# ADC.net
KiCad netlist of a schematic drawn in Altium Designer
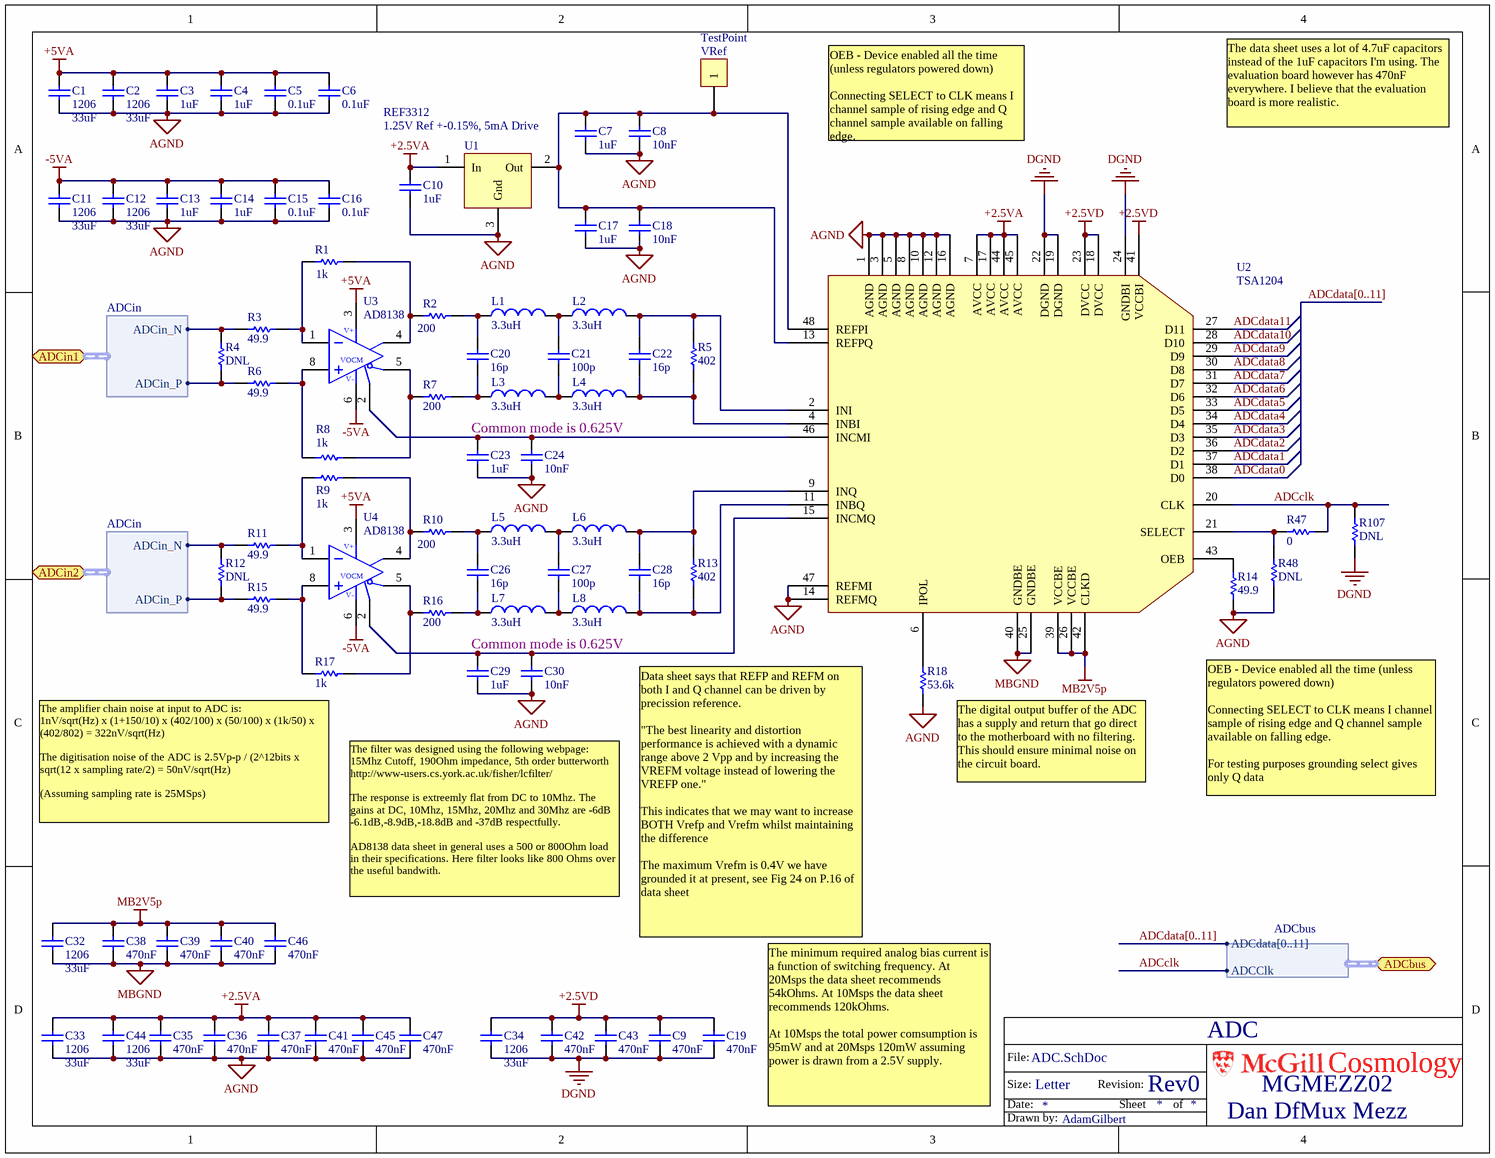
[diagram p0: ADC.SchDoc]

(export (version "E")
  (design (tool "Eeschema 10.0.6"))
  (components
    (comp (ref "C1")
      (value "33uF")
      (footprint "1206")
      (description "Capacitor, Ceramic, 1210")
      (fields
        (field (name "MANUFACTURER") "TDK Corporation")
        (field (name "MANUFACTURERS PART NUMBER") "C3216X5R1E336M")
      )
      (libsource (lib "MGMEZZ04") (part "CAP 1210"))
    )
    (comp (ref "C2")
      (value "33uF")
      (footprint "1206")
      (description "Capacitor, Ceramic, 1210")
      (fields
        (field (name "MANUFACTURER") "TDK Corporation")
        (field (name "MANUFACTURERS PART NUMBER") "C3216X5R1E336M")
      )
      (libsource (lib "MGMEZZ04") (part "CAP 1210"))
    )
    (comp (ref "C3")
      (value "1uF")
      (footprint "0603")
      (description "Capacitor, Ceramic, 0603")
      (fields
        (field (name "MANUFACTURER") "Generic")
        (field (name "MANUFACTURERS PART NUMBER") "e.g C1608X7R1C105K")
      )
      (libsource (lib "MGMEZZ04") (part "CAP 0603"))
    )
    (comp (ref "C4")
      (value "1uF")
      (footprint "0603")
      (description "Capacitor, Ceramic, 0603")
      (fields
        (field (name "MANUFACTURER") "Generic")
        (field (name "MANUFACTURERS PART NUMBER") "e.g C1608X7R1C105K")
      )
      (libsource (lib "MGMEZZ04") (part "CAP 0603"))
    )
    (comp (ref "C5")
      (value "0.1uF")
      (footprint "0603")
      (description "Capacitor, Ceramic, 0603")
      (fields (field (name "MANUFACTURER") "Generic"))
      (libsource (lib "MGMEZZ04") (part "CAP 0603"))
    )
    (comp (ref "C6")
      (value "0.1uF")
      (footprint "0603")
      (description "Capacitor, Ceramic, 0603")
      (fields (field (name "MANUFACTURER") "Generic"))
      (libsource (lib "MGMEZZ04") (part "CAP 0603"))
    )
    (comp (ref "C7")
      (value "1uF")
      (footprint "0603")
      (description "Capacitor, Ceramic, 0603")
      (fields
        (field (name "MANUFACTURER") "Generic")
        (field (name "MANUFACTURERS PART NUMBER") "e.g C1608X7R1C105K")
      )
      (libsource (lib "MGMEZZ04") (part "CAP 0603"))
    )
    (comp (ref "C8")
      (value "10nF")
      (footprint "0603")
      (description "Capacitor, Ceramic, 0603")
      (fields (field (name "MANUFACTURER") "Generic"))
      (libsource (lib "MGMEZZ04") (part "CAP 0603"))
    )
    (comp (ref "C9")
      (value "470nF")
      (footprint "0603")
      (description "Capacitor, Ceramic, 0603")
      (fields (field (name "MANUFACTURER") "Generic"))
      (libsource (lib "MGMEZZ04") (part "CAP 0603"))
    )
    (comp (ref "C10")
      (value "1uF")
      (footprint "0603")
      (description "Capacitor, Ceramic, 0603")
      (fields
        (field (name "MANUFACTURER") "Generic")
        (field (name "MANUFACTURERS PART NUMBER") "e.g C1608X7R1C105K")
      )
      (libsource (lib "MGMEZZ04") (part "CAP 0603"))
    )
    (comp (ref "C11")
      (value "33uF")
      (footprint "1206")
      (description "Capacitor, Ceramic, 1210")
      (fields
        (field (name "MANUFACTURER") "TDK Corporation")
        (field (name "MANUFACTURERS PART NUMBER") "C3216X5R1E336M")
      )
      (libsource (lib "MGMEZZ04") (part "CAP 1210"))
    )
    (comp (ref "C12")
      (value "33uF")
      (footprint "1206")
      (description "Capacitor, Ceramic, 1210")
      (fields
        (field (name "MANUFACTURER") "TDK Corporation")
        (field (name "MANUFACTURERS PART NUMBER") "C3216X5R1E336M")
      )
      (libsource (lib "MGMEZZ04") (part "CAP 1210"))
    )
    (comp (ref "C13")
      (value "1uF")
      (footprint "0603")
      (description "Capacitor, Ceramic, 0603")
      (fields
        (field (name "MANUFACTURER") "Generic")
        (field (name "MANUFACTURERS PART NUMBER") "e.g C1608X7R1C105K")
      )
      (libsource (lib "MGMEZZ04") (part "CAP 0603"))
    )
    (comp (ref "C14")
      (value "1uF")
      (footprint "0603")
      (description "Capacitor, Ceramic, 0603")
      (fields
        (field (name "MANUFACTURER") "Generic")
        (field (name "MANUFACTURERS PART NUMBER") "e.g C1608X7R1C105K")
      )
      (libsource (lib "MGMEZZ04") (part "CAP 0603"))
    )
    (comp (ref "C15")
      (value "0.1uF")
      (footprint "0603")
      (description "Capacitor, Ceramic, 0603")
      (fields (field (name "MANUFACTURER") "Generic"))
      (libsource (lib "MGMEZZ04") (part "CAP 0603"))
    )
    (comp (ref "C16")
      (value "0.1uF")
      (footprint "0603")
      (description "Capacitor, Ceramic, 0603")
      (fields (field (name "MANUFACTURER") "Generic"))
      (libsource (lib "MGMEZZ04") (part "CAP 0603"))
    )
    (comp (ref "C17")
      (value "1uF")
      (footprint "0603")
      (description "Capacitor, Ceramic, 0603")
      (fields
        (field (name "MANUFACTURER") "Generic")
        (field (name "MANUFACTURERS PART NUMBER") "e.g C1608X7R1C105K")
      )
      (libsource (lib "MGMEZZ04") (part "CAP 0603"))
    )
    (comp (ref "C18")
      (value "10nF")
      (footprint "0603")
      (description "Capacitor, Ceramic, 0603")
      (fields (field (name "MANUFACTURER") "Generic"))
      (libsource (lib "MGMEZZ04") (part "CAP 0603"))
    )
    (comp (ref "C19")
      (value "470nF")
      (footprint "0603")
      (description "Capacitor, Ceramic, 0603")
      (fields (field (name "MANUFACTURER") "Generic"))
      (libsource (lib "MGMEZZ04") (part "CAP 0603"))
    )
    (comp (ref "C20")
      (value "16p")
      (footprint "0603")
      (description "Capacitor, Ceramic, 0603")
      (fields (field (name "MANUFACTURER") "Generic"))
      (libsource (lib "MGMEZZ04") (part "CAP 0603"))
    )
    (comp (ref "C21")
      (value "100p")
      (footprint "0603")
      (description "Capacitor, Ceramic, 0603")
      (fields (field (name "MANUFACTURER") "Generic"))
      (libsource (lib "MGMEZZ04") (part "CAP 0603"))
    )
    (comp (ref "C22")
      (value "16p")
      (footprint "0603")
      (description "Capacitor, Ceramic, 0603")
      (fields (field (name "MANUFACTURER") "Generic"))
      (libsource (lib "MGMEZZ04") (part "CAP 0603"))
    )
    (comp (ref "C23")
      (value "1uF")
      (footprint "0603")
      (description "Capacitor, Ceramic, 0603")
      (fields
        (field (name "MANUFACTURER") "Generic")
        (field (name "MANUFACTURERS PART NUMBER") "e.g C1608X7R1C105K")
      )
      (libsource (lib "MGMEZZ04") (part "CAP 0603"))
    )
    (comp (ref "C24")
      (value "10nF")
      (footprint "0603")
      (description "Capacitor, Ceramic, 0603")
      (fields (field (name "MANUFACTURER") "Generic"))
      (libsource (lib "MGMEZZ04") (part "CAP 0603"))
    )
    (comp (ref "C26")
      (value "16p")
      (footprint "0603")
      (description "Capacitor, Ceramic, 0603")
      (fields (field (name "MANUFACTURER") "Generic"))
      (libsource (lib "MGMEZZ04") (part "CAP 0603"))
    )
    (comp (ref "C27")
      (value "100p")
      (footprint "0603")
      (description "Capacitor, Ceramic, 0603")
      (fields (field (name "MANUFACTURER") "Generic"))
      (libsource (lib "MGMEZZ04") (part "CAP 0603"))
    )
    (comp (ref "C28")
      (value "16p")
      (footprint "0603")
      (description "Capacitor, Ceramic, 0603")
      (fields (field (name "MANUFACTURER") "Generic"))
      (libsource (lib "MGMEZZ04") (part "CAP 0603"))
    )
    (comp (ref "C29")
      (value "1uF")
      (footprint "0603")
      (description "Capacitor, Ceramic, 0603")
      (fields
        (field (name "MANUFACTURER") "Generic")
        (field (name "MANUFACTURERS PART NUMBER") "e.g C1608X7R1C105K")
      )
      (libsource (lib "MGMEZZ04") (part "CAP 0603"))
    )
    (comp (ref "C30")
      (value "10nF")
      (footprint "0603")
      (description "Capacitor, Ceramic, 0603")
      (fields (field (name "MANUFACTURER") "Generic"))
      (libsource (lib "MGMEZZ04") (part "CAP 0603"))
    )
    (comp (ref "C32")
      (value "33uF")
      (footprint "1206")
      (description "Capacitor, Ceramic, 1210")
      (fields
        (field (name "MANUFACTURER") "TDK Corporation")
        (field (name "MANUFACTURERS PART NUMBER") "C3216X5R1E336M")
      )
      (libsource (lib "MGMEZZ04") (part "CAP 1210"))
    )
    (comp (ref "C33")
      (value "33uF")
      (footprint "1206")
      (description "Capacitor, Ceramic, 1210")
      (fields
        (field (name "MANUFACTURER") "TDK Corporation")
        (field (name "MANUFACTURERS PART NUMBER") "C3216X5R1E336M")
      )
      (libsource (lib "MGMEZZ04") (part "CAP 1210"))
    )
    (comp (ref "C34")
      (value "33uF")
      (footprint "1206")
      (description "Capacitor, Ceramic, 1210")
      (fields
        (field (name "MANUFACTURER") "TDK Corporation")
        (field (name "MANUFACTURERS PART NUMBER") "C3216X5R1E336M")
      )
      (libsource (lib "MGMEZZ04") (part "CAP 1210"))
    )
    (comp (ref "C35")
      (value "470nF")
      (footprint "0603")
      (description "Capacitor, Ceramic, 0603")
      (fields (field (name "MANUFACTURER") "Generic"))
      (libsource (lib "MGMEZZ04") (part "CAP 0603"))
    )
    (comp (ref "C36")
      (value "470nF")
      (footprint "0603")
      (description "Capacitor, Ceramic, 0603")
      (fields (field (name "MANUFACTURER") "Generic"))
      (libsource (lib "MGMEZZ04") (part "CAP 0603"))
    )
    (comp (ref "C37")
      (value "470nF")
      (footprint "0603")
      (description "Capacitor, Ceramic, 0603")
      (fields (field (name "MANUFACTURER") "Generic"))
      (libsource (lib "MGMEZZ04") (part "CAP 0603"))
    )
    (comp (ref "C38")
      (value "470nF")
      (footprint "0603")
      (description "Capacitor, Ceramic, 0603")
      (fields (field (name "MANUFACTURER") "Generic"))
      (libsource (lib "MGMEZZ04") (part "CAP 0603"))
    )
    (comp (ref "C39")
      (value "470nF")
      (footprint "0603")
      (description "Capacitor, Ceramic, 0603")
      (fields (field (name "MANUFACTURER") "Generic"))
      (libsource (lib "MGMEZZ04") (part "CAP 0603"))
    )
    (comp (ref "C40")
      (value "470nF")
      (footprint "0603")
      (description "Capacitor, Ceramic, 0603")
      (fields (field (name "MANUFACTURER") "Generic"))
      (libsource (lib "MGMEZZ04") (part "CAP 0603"))
    )
    (comp (ref "C41")
      (value "470nF")
      (footprint "0603")
      (description "Capacitor, Ceramic, 0603")
      (fields (field (name "MANUFACTURER") "Generic"))
      (libsource (lib "MGMEZZ04") (part "CAP 0603"))
    )
    (comp (ref "C42")
      (value "470nF")
      (footprint "0603")
      (description "Capacitor, Ceramic, 0603")
      (fields (field (name "MANUFACTURER") "Generic"))
      (libsource (lib "MGMEZZ04") (part "CAP 0603"))
    )
    (comp (ref "C43")
      (value "470nF")
      (footprint "0603")
      (description "Capacitor, Ceramic, 0603")
      (fields (field (name "MANUFACTURER") "Generic"))
      (libsource (lib "MGMEZZ04") (part "CAP 0603"))
    )
    (comp (ref "C44")
      (value "33uF")
      (footprint "1206")
      (description "Capacitor, Ceramic, 1210")
      (fields
        (field (name "MANUFACTURER") "TDK Corporation")
        (field (name "MANUFACTURERS PART NUMBER") "C3216X5R1E336M")
      )
      (libsource (lib "MGMEZZ04") (part "CAP 1210"))
    )
    (comp (ref "C45")
      (value "470nF")
      (footprint "0603")
      (description "Capacitor, Ceramic, 0603")
      (fields (field (name "MANUFACTURER") "Generic"))
      (libsource (lib "MGMEZZ04") (part "CAP 0603"))
    )
    (comp (ref "C46")
      (value "470nF")
      (footprint "0603")
      (description "Capacitor, Ceramic, 0603")
      (fields (field (name "MANUFACTURER") "Generic"))
      (libsource (lib "MGMEZZ04") (part "CAP 0603"))
    )
    (comp (ref "C47")
      (value "470nF")
      (footprint "0603")
      (description "Capacitor, Ceramic, 0603")
      (fields (field (name "MANUFACTURER") "Generic"))
      (libsource (lib "MGMEZZ04") (part "CAP 0603"))
    )
    (comp (ref "L1")
      (value "3.3uH")
      (footprint "0603")
      (description "Inductor 0603")
      (fields
        (field (name "MANUFACTURER") "TDK Coporation")
        (field (name "MANUFACTURERS PART NUMBER") "MLF1608A4R7K")
      )
      (libsource (lib "MGMEZZ04") (part "IND 0603"))
    )
    (comp (ref "L2")
      (value "3.3uH")
      (footprint "0603")
      (description "Inductor 0603")
      (fields
        (field (name "MANUFACTURER") "TDK Coporation")
        (field (name "MANUFACTURERS PART NUMBER") "MLF1608A4R7K")
      )
      (libsource (lib "MGMEZZ04") (part "IND 0603"))
    )
    (comp (ref "L3")
      (value "3.3uH")
      (footprint "0603")
      (description "Inductor 0603")
      (fields
        (field (name "MANUFACTURER") "TDK Coporation")
        (field (name "MANUFACTURERS PART NUMBER") "MLF1608A4R7K")
      )
      (libsource (lib "MGMEZZ04") (part "IND 0603"))
    )
    (comp (ref "L4")
      (value "3.3uH")
      (footprint "0603")
      (description "Inductor 0603")
      (fields
        (field (name "MANUFACTURER") "TDK Coporation")
        (field (name "MANUFACTURERS PART NUMBER") "MLF1608A4R7K")
      )
      (libsource (lib "MGMEZZ04") (part "IND 0603"))
    )
    (comp (ref "L5")
      (value "3.3uH")
      (footprint "0603")
      (description "Inductor 0603")
      (fields
        (field (name "MANUFACTURER") "TDK Coporation")
        (field (name "MANUFACTURERS PART NUMBER") "MLF1608A4R7K")
      )
      (libsource (lib "MGMEZZ04") (part "IND 0603"))
    )
    (comp (ref "L6")
      (value "3.3uH")
      (footprint "0603")
      (description "Inductor 0603")
      (fields
        (field (name "MANUFACTURER") "TDK Coporation")
        (field (name "MANUFACTURERS PART NUMBER") "MLF1608A4R7K")
      )
      (libsource (lib "MGMEZZ04") (part "IND 0603"))
    )
    (comp (ref "L7")
      (value "3.3uH")
      (footprint "0603")
      (description "Inductor 0603")
      (fields
        (field (name "MANUFACTURER") "TDK Coporation")
        (field (name "MANUFACTURERS PART NUMBER") "MLF1608A4R7K")
      )
      (libsource (lib "MGMEZZ04") (part "IND 0603"))
    )
    (comp (ref "L8")
      (value "3.3uH")
      (footprint "0603")
      (description "Inductor 0603")
      (fields
        (field (name "MANUFACTURER") "TDK Coporation")
        (field (name "MANUFACTURERS PART NUMBER") "MLF1608A4R7K")
      )
      (libsource (lib "MGMEZZ04") (part "IND 0603"))
    )
    (comp (ref "R1")
      (value "1k")
      (footprint "0603")
      (description "Resistor")
      (fields (field (name "MANUFACTURER") "Generic"))
      (libsource (lib "MGMEZZ04") (part "RES 0603"))
    )
    (comp (ref "R2")
      (value "200")
      (footprint "0603")
      (description "Resistor")
      (fields (field (name "MANUFACTURER") "Generic"))
      (libsource (lib "MGMEZZ04") (part "RES 0603"))
    )
    (comp (ref "R3")
      (value "49.9")
      (footprint "0603")
      (description "Resistor")
      (fields (field (name "MANUFACTURER") "Generic"))
      (libsource (lib "MGMEZZ04") (part "RES 0603"))
    )
    (comp (ref "R4")
      (value "DNL")
      (footprint "0603")
      (description "Resistor")
      (fields (field (name "MANUFACTURER") "Generic"))
      (libsource (lib "MGMEZZ04") (part "RES 0603"))
    )
    (comp (ref "R5")
      (value "402")
      (footprint "0603")
      (description "Resistor")
      (fields (field (name "MANUFACTURER") "Generic"))
      (libsource (lib "MGMEZZ04") (part "RES 0603"))
    )
    (comp (ref "R6")
      (value "49.9")
      (footprint "0603")
      (description "Resistor")
      (fields (field (name "MANUFACTURER") "Generic"))
      (libsource (lib "MGMEZZ04") (part "RES 0603"))
    )
    (comp (ref "R7")
      (value "200")
      (footprint "0603")
      (description "Resistor")
      (fields (field (name "MANUFACTURER") "Generic"))
      (libsource (lib "MGMEZZ04") (part "RES 0603"))
    )
    (comp (ref "R8")
      (value "1k")
      (footprint "0603")
      (description "Resistor")
      (fields (field (name "MANUFACTURER") "Generic"))
      (libsource (lib "MGMEZZ04") (part "RES 0603"))
    )
    (comp (ref "R9")
      (value "1k")
      (footprint "0603")
      (description "Resistor")
      (fields (field (name "MANUFACTURER") "Generic"))
      (libsource (lib "MGMEZZ04") (part "RES 0603"))
    )
    (comp (ref "R10")
      (value "200")
      (footprint "0603")
      (description "Resistor")
      (fields (field (name "MANUFACTURER") "Generic"))
      (libsource (lib "MGMEZZ04") (part "RES 0603"))
    )
    (comp (ref "R11")
      (value "49.9")
      (footprint "0603")
      (description "Resistor")
      (fields (field (name "MANUFACTURER") "Generic"))
      (libsource (lib "MGMEZZ04") (part "RES 0603"))
    )
    (comp (ref "R12")
      (value "DNL")
      (footprint "0603")
      (description "Resistor")
      (fields (field (name "MANUFACTURER") "Generic"))
      (libsource (lib "MGMEZZ04") (part "RES 0603"))
    )
    (comp (ref "R13")
      (value "402")
      (footprint "0603")
      (description "Resistor")
      (fields (field (name "MANUFACTURER") "Generic"))
      (libsource (lib "MGMEZZ04") (part "RES 0603"))
    )
    (comp (ref "R14")
      (value "49.9")
      (footprint "0603")
      (description "Resistor")
      (fields (field (name "MANUFACTURER") "Generic"))
      (libsource (lib "MGMEZZ04") (part "RES 0603"))
    )
    (comp (ref "R15")
      (value "49.9")
      (footprint "0603")
      (description "Resistor")
      (fields (field (name "MANUFACTURER") "Generic"))
      (libsource (lib "MGMEZZ04") (part "RES 0603"))
    )
    (comp (ref "R16")
      (value "200")
      (footprint "0603")
      (description "Resistor")
      (fields (field (name "MANUFACTURER") "Generic"))
      (libsource (lib "MGMEZZ04") (part "RES 0603"))
    )
    (comp (ref "R17")
      (value "1k")
      (footprint "0603")
      (description "Resistor")
      (fields (field (name "MANUFACTURER") "Generic"))
      (libsource (lib "MGMEZZ04") (part "RES 0603"))
    )
    (comp (ref "R18")
      (value "53.6k")
      (footprint "0603")
      (description "Resistor")
      (fields (field (name "MANUFACTURER") "Generic"))
      (libsource (lib "MGMEZZ04") (part "RES 0603"))
    )
    (comp (ref "R47")
      (value "0")
      (footprint "0603")
      (description "Resistor")
      (fields (field (name "MANUFACTURER") "Generic"))
      (libsource (lib "MGMEZZ04") (part "RES 0603"))
    )
    (comp (ref "R48")
      (value "DNL")
      (footprint "0603")
      (description "Resistor")
      (fields (field (name "MANUFACTURER") "Generic"))
      (libsource (lib "MGMEZZ04") (part "RES 0603"))
    )
    (comp (ref "R107")
      (value "DNL")
      (footprint "0603")
      (description "Resistor")
      (fields (field (name "MANUFACTURER") "Generic"))
      (libsource (lib "MGMEZZ04") (part "RES 0603"))
    )
    (comp (ref "U1")
      (value "REF3312")
      (footprint "SOT23")
      (description "1.25V Ref +-0.15%, 5mA Drive")
      (fields
        (field (name "MANUFACTURER") "Texas Instruments")
        (field (name "MANUFACTURERS PART NUMBER") "REF3312AIDBZT")
      )
      (libsource (lib "MGMEZZ04") (part "REF3312AIDBZT"))
    )
    (comp (ref "U2")
      (value "TSA1204")
      (footprint "TSQFP50P900X900X160-48N")
      (description "ADC 2-Channel 12bit")
      (fields
        (field (name "MANUFACTURERS PART NUMBER") "TSA1204IFT")
        (field (name "MANUFACTURER") "STMicroelectronics")
      )
      (libsource (lib "MGMEZZ04") (part "TSA1204"))
    )
    (comp (ref "U3")
      (value "AD8138")
      (footprint "SO8")
      (description "IC AMP DIFF LDIST LP 95MA 8SOIC")
      (fields
        (field (name "MANUFACTURER") "Analog Devices Inc")
        (field (name "MANUFACTURERS PART NUMBER") "AD8138ARZ")
      )
      (libsource (lib "MGMEZZ04") (part "AD8138"))
    )
    (comp (ref "U4")
      (value "AD8138")
      (footprint "SO8")
      (description "IC AMP DIFF LDIST LP 95MA 8SOIC")
      (fields
        (field (name "MANUFACTURER") "Analog Devices Inc")
        (field (name "MANUFACTURERS PART NUMBER") "AD8138ARZ")
      )
      (libsource (lib "MGMEZZ04") (part "AD8138"))
    )
    (comp (ref "VRef")
      (value "TestPoint")
      (footprint "TP-3520-SK")
      (description "TestPoint1")
      (libsource (lib "MGMEZZ04") (part "TestPoint"))
    )
  )
  (nets
    (net (code "3") (name "+2.5VA") (class "Default")
      (node (ref "C10") (pin "2") (pinfunction "2_2") (pintype "passive"))
      (node (ref "C33") (pin "2") (pinfunction "2_2") (pintype "passive"))
      (node (ref "C35") (pin "2") (pinfunction "2_2") (pintype "passive"))
      (node (ref "C36") (pin "2") (pinfunction "2_2") (pintype "passive"))
      (node (ref "C37") (pin "2") (pinfunction "2_2") (pintype "passive"))
      (node (ref "C41") (pin "2") (pinfunction "2_2") (pintype "passive"))
      (node (ref "C44") (pin "2") (pinfunction "2_2") (pintype "passive"))
      (node (ref "C45") (pin "2") (pinfunction "2_2") (pintype "passive"))
      (node (ref "C47") (pin "2") (pinfunction "2_2") (pintype "passive"))
      (node (ref "U1") (pin "1") (pinfunction "In_1") (pintype "passive"))
      (node (ref "U2") (pin "17") (pinfunction "AVCC_17") (pintype "passive"))
      (node (ref "U2") (pin "44") (pinfunction "AVCC_44") (pintype "passive"))
      (node (ref "U2") (pin "45") (pinfunction "AVCC_45") (pintype "passive"))
      (node (ref "U2") (pin "7") (pinfunction "AVCC_7") (pintype "passive"))
    )
    (net (code "4") (name "+2.5VD") (class "Default")
      (node (ref "C19") (pin "2") (pinfunction "2_2") (pintype "passive"))
      (node (ref "C34") (pin "2") (pinfunction "2_2") (pintype "passive"))
      (node (ref "C42") (pin "2") (pinfunction "2_2") (pintype "passive"))
      (node (ref "C43") (pin "2") (pinfunction "2_2") (pintype "passive"))
      (node (ref "C9") (pin "2") (pinfunction "2_2") (pintype "passive"))
      (node (ref "U2") (pin "18") (pinfunction "DVCC_18") (pintype "passive"))
      (node (ref "U2") (pin "23") (pinfunction "DVCC_23") (pintype "passive"))
      (node (ref "U2") (pin "41") (pinfunction "VCCBI_41") (pintype "passive"))
    )
    (net (code "5") (name "+5VA") (class "Default")
      (node (ref "C1") (pin "2") (pinfunction "2_2") (pintype "passive"))
      (node (ref "C2") (pin "2") (pinfunction "2_2") (pintype "passive"))
      (node (ref "C3") (pin "2") (pinfunction "2_2") (pintype "passive"))
      (node (ref "C4") (pin "2") (pinfunction "2_2") (pintype "passive"))
      (node (ref "C5") (pin "1") (pinfunction "1_1") (pintype "passive"))
      (node (ref "C6") (pin "1") (pinfunction "1_1") (pintype "passive"))
      (node (ref "U3") (pin "3") (pinfunction "V+_3") (pintype "power_in"))
      (node (ref "U4") (pin "3") (pinfunction "V+_3") (pintype "power_in"))
    )
    (net (code "6") (name "-5VA") (class "Default")
      (node (ref "C11") (pin "2") (pinfunction "2_2") (pintype "passive"))
      (node (ref "C12") (pin "2") (pinfunction "2_2") (pintype "passive"))
      (node (ref "C13") (pin "2") (pinfunction "2_2") (pintype "passive"))
      (node (ref "C14") (pin "2") (pinfunction "2_2") (pintype "passive"))
      (node (ref "C15") (pin "1") (pinfunction "1_1") (pintype "passive"))
      (node (ref "C16") (pin "1") (pinfunction "1_1") (pintype "passive"))
      (node (ref "U3") (pin "6") (pinfunction "V-_6") (pintype "power_in"))
      (node (ref "U4") (pin "6") (pinfunction "V-_6") (pintype "power_in"))
    )
    (net (code "8") (name "/ADCclk") (class "Default")
      (node (ref "R107") (pin "2") (pinfunction "2_2") (pintype "passive"))
      (node (ref "R47") (pin "1") (pinfunction "1_1") (pintype "passive"))
      (node (ref "U2") (pin "20") (pinfunction "CLK_20") (pintype "passive"))
    )
    (net (code "9") (name "/ADCdata0") (class "Default")
      (node (ref "U2") (pin "38") (pinfunction "D0_38") (pintype "passive"))
    )
    (net (code "10") (name "/ADCdata1") (class "Default")
      (node (ref "U2") (pin "37") (pinfunction "D1_37") (pintype "passive"))
    )
    (net (code "11") (name "/ADCdata2") (class "Default")
      (node (ref "U2") (pin "36") (pinfunction "D2_36") (pintype "passive"))
    )
    (net (code "12") (name "/ADCdata3") (class "Default")
      (node (ref "U2") (pin "35") (pinfunction "D3_35") (pintype "passive"))
    )
    (net (code "13") (name "/ADCdata4") (class "Default")
      (node (ref "U2") (pin "34") (pinfunction "D4_34") (pintype "passive"))
    )
    (net (code "14") (name "/ADCdata5") (class "Default")
      (node (ref "U2") (pin "33") (pinfunction "D5_33") (pintype "passive"))
    )
    (net (code "15") (name "/ADCdata6") (class "Default")
      (node (ref "U2") (pin "32") (pinfunction "D6_32") (pintype "passive"))
    )
    (net (code "16") (name "/ADCdata7") (class "Default")
      (node (ref "U2") (pin "31") (pinfunction "D7_31") (pintype "passive"))
    )
    (net (code "17") (name "/ADCdata8") (class "Default")
      (node (ref "U2") (pin "30") (pinfunction "D8_30") (pintype "passive"))
    )
    (net (code "18") (name "/ADCdata9") (class "Default")
      (node (ref "U2") (pin "29") (pinfunction "D9_29") (pintype "passive"))
    )
    (net (code "19") (name "/ADCdata10") (class "Default")
      (node (ref "U2") (pin "28") (pinfunction "D10_28") (pintype "passive"))
    )
    (net (code "20") (name "/ADCdata11") (class "Default")
      (node (ref "U2") (pin "27") (pinfunction "D11_27") (pintype "passive"))
    )
    (net (code "24") (name "AGND") (class "Default")
      (node (ref "C1") (pin "1") (pinfunction "1_1") (pintype "passive"))
      (node (ref "C10") (pin "1") (pinfunction "1_1") (pintype "passive"))
      (node (ref "C11") (pin "1") (pinfunction "1_1") (pintype "passive"))
      (node (ref "C12") (pin "1") (pinfunction "1_1") (pintype "passive"))
      (node (ref "C13") (pin "1") (pinfunction "1_1") (pintype "passive"))
      (node (ref "C14") (pin "1") (pinfunction "1_1") (pintype "passive"))
      (node (ref "C15") (pin "2") (pinfunction "2_2") (pintype "passive"))
      (node (ref "C16") (pin "2") (pinfunction "2_2") (pintype "passive"))
      (node (ref "C17") (pin "1") (pinfunction "1_1") (pintype "passive"))
      (node (ref "C18") (pin "1") (pinfunction "1_1") (pintype "passive"))
      (node (ref "C2") (pin "1") (pinfunction "1_1") (pintype "passive"))
      (node (ref "C23") (pin "1") (pinfunction "1_1") (pintype "passive"))
      (node (ref "C24") (pin "1") (pinfunction "1_1") (pintype "passive"))
      (node (ref "C29") (pin "1") (pinfunction "1_1") (pintype "passive"))
      (node (ref "C3") (pin "1") (pinfunction "1_1") (pintype "passive"))
      (node (ref "C30") (pin "1") (pinfunction "1_1") (pintype "passive"))
      (node (ref "C33") (pin "1") (pinfunction "1_1") (pintype "passive"))
      (node (ref "C35") (pin "1") (pinfunction "1_1") (pintype "passive"))
      (node (ref "C36") (pin "1") (pinfunction "1_1") (pintype "passive"))
      (node (ref "C37") (pin "1") (pinfunction "1_1") (pintype "passive"))
      (node (ref "C4") (pin "1") (pinfunction "1_1") (pintype "passive"))
      (node (ref "C41") (pin "1") (pinfunction "1_1") (pintype "passive"))
      (node (ref "C44") (pin "1") (pinfunction "1_1") (pintype "passive"))
      (node (ref "C45") (pin "1") (pinfunction "1_1") (pintype "passive"))
      (node (ref "C47") (pin "1") (pinfunction "1_1") (pintype "passive"))
      (node (ref "C5") (pin "2") (pinfunction "2_2") (pintype "passive"))
      (node (ref "C6") (pin "2") (pinfunction "2_2") (pintype "passive"))
      (node (ref "C7") (pin "1") (pinfunction "1_1") (pintype "passive"))
      (node (ref "C8") (pin "1") (pinfunction "1_1") (pintype "passive"))
      (node (ref "R14") (pin "1") (pinfunction "1_1") (pintype "passive"))
      (node (ref "R18") (pin "1") (pinfunction "1_1") (pintype "passive"))
      (node (ref "R48") (pin "2") (pinfunction "2_2") (pintype "passive"))
      (node (ref "U1") (pin "3") (pinfunction "Gnd_3") (pintype "passive"))
      (node (ref "U2") (pin "1") (pinfunction "AGND_1") (pintype "passive"))
      (node (ref "U2") (pin "10") (pinfunction "AGND_10") (pintype "passive"))
      (node (ref "U2") (pin "12") (pinfunction "AGND_12") (pintype "passive"))
      (node (ref "U2") (pin "14") (pinfunction "REFMQ_14") (pintype "passive"))
      (node (ref "U2") (pin "16") (pinfunction "AGND_16") (pintype "passive"))
      (node (ref "U2") (pin "3") (pinfunction "AGND_3") (pintype "passive"))
      (node (ref "U2") (pin "47") (pinfunction "REFMI_47") (pintype "passive"))
      (node (ref "U2") (pin "5") (pinfunction "AGND_5") (pintype "passive"))
      (node (ref "U2") (pin "8") (pinfunction "AGND_8") (pintype "passive"))
    )
    (net (code "25") (name "DGND") (class "Default")
      (node (ref "C19") (pin "1") (pinfunction "1_1") (pintype "passive"))
      (node (ref "C34") (pin "1") (pinfunction "1_1") (pintype "passive"))
      (node (ref "C42") (pin "1") (pinfunction "1_1") (pintype "passive"))
      (node (ref "C43") (pin "1") (pinfunction "1_1") (pintype "passive"))
      (node (ref "C9") (pin "1") (pinfunction "1_1") (pintype "passive"))
      (node (ref "R107") (pin "1") (pinfunction "1_1") (pintype "passive"))
      (node (ref "U2") (pin "19") (pinfunction "DGND_19") (pintype "passive"))
      (node (ref "U2") (pin "22") (pinfunction "DGND_22") (pintype "passive"))
      (node (ref "U2") (pin "24") (pinfunction "GNDBI_24") (pintype "passive"))
    )
    (net (code "26") (name "MB2V5p") (class "Default")
      (node (ref "C32") (pin "2") (pinfunction "2_2") (pintype "passive"))
      (node (ref "C38") (pin "2") (pinfunction "2_2") (pintype "passive"))
      (node (ref "C39") (pin "2") (pinfunction "2_2") (pintype "passive"))
      (node (ref "C40") (pin "2") (pinfunction "2_2") (pintype "passive"))
      (node (ref "C46") (pin "2") (pinfunction "2_2") (pintype "passive"))
      (node (ref "U2") (pin "26") (pinfunction "VCCBE_26") (pintype "passive"))
      (node (ref "U2") (pin "39") (pinfunction "VCCBE_39") (pintype "passive"))
      (node (ref "U2") (pin "42") (pinfunction "CLKD_42") (pintype "passive"))
    )
    (net (code "27") (name "MBGND") (class "Default")
      (node (ref "C32") (pin "1") (pinfunction "1_1") (pintype "passive"))
      (node (ref "C38") (pin "1") (pinfunction "1_1") (pintype "passive"))
      (node (ref "C39") (pin "1") (pinfunction "1_1") (pintype "passive"))
      (node (ref "C40") (pin "1") (pinfunction "1_1") (pintype "passive"))
      (node (ref "C46") (pin "1") (pinfunction "1_1") (pintype "passive"))
      (node (ref "U2") (pin "25") (pinfunction "GNDBE_25") (pintype "passive"))
      (node (ref "U2") (pin "40") (pinfunction "GNDBE_40") (pintype "passive"))
    )
    (net (code "28") (name "Net-(C20-Pad1)") (class "Default")
      (node (ref "C20") (pin "1") (pinfunction "1_1") (pintype "passive"))
      (node (ref "L3") (pin "1") (pinfunction "1_1") (pintype "passive"))
      (node (ref "R7") (pin "1") (pinfunction "1_1") (pintype "passive"))
    )
    (net (code "29") (name "Net-(C20-Pad2)") (class "Default")
      (node (ref "C20") (pin "2") (pinfunction "2_2") (pintype "passive"))
      (node (ref "L1") (pin "1") (pinfunction "1_1") (pintype "passive"))
      (node (ref "R2") (pin "1") (pinfunction "1_1") (pintype "passive"))
    )
    (net (code "30") (name "Net-(C21-Pad1)") (class "Default")
      (node (ref "C21") (pin "1") (pinfunction "1_1") (pintype "passive"))
      (node (ref "L3") (pin "2") (pinfunction "2_2") (pintype "passive"))
      (node (ref "L4") (pin "1") (pinfunction "1_1") (pintype "passive"))
    )
    (net (code "31") (name "Net-(C21-Pad2)") (class "Default")
      (node (ref "C21") (pin "2") (pinfunction "2_2") (pintype "passive"))
      (node (ref "L1") (pin "2") (pinfunction "2_2") (pintype "passive"))
      (node (ref "L2") (pin "1") (pinfunction "1_1") (pintype "passive"))
    )
    (net (code "32") (name "Net-(C26-Pad1)") (class "Default")
      (node (ref "C26") (pin "1") (pinfunction "1_1") (pintype "passive"))
      (node (ref "L7") (pin "1") (pinfunction "1_1") (pintype "passive"))
      (node (ref "R16") (pin "1") (pinfunction "1_1") (pintype "passive"))
    )
    (net (code "33") (name "Net-(C26-Pad2)") (class "Default")
      (node (ref "C26") (pin "2") (pinfunction "2_2") (pintype "passive"))
      (node (ref "L5") (pin "1") (pinfunction "1_1") (pintype "passive"))
      (node (ref "R10") (pin "1") (pinfunction "1_1") (pintype "passive"))
    )
    (net (code "34") (name "Net-(C27-Pad1)") (class "Default")
      (node (ref "C27") (pin "1") (pinfunction "1_1") (pintype "passive"))
      (node (ref "L7") (pin "2") (pinfunction "2_2") (pintype "passive"))
      (node (ref "L8") (pin "1") (pinfunction "1_1") (pintype "passive"))
    )
    (net (code "35") (name "Net-(C27-Pad2)") (class "Default")
      (node (ref "C27") (pin "2") (pinfunction "2_2") (pintype "passive"))
      (node (ref "L5") (pin "2") (pinfunction "2_2") (pintype "passive"))
      (node (ref "L6") (pin "1") (pinfunction "1_1") (pintype "passive"))
    )
    (net (code "36") (name "Net-(R3-Pad2)") (class "Default")
      (node (ref "R3") (pin "2") (pinfunction "2_2") (pintype "passive"))
      (node (ref "R4") (pin "2") (pinfunction "2_2") (pintype "passive"))
    )
    (net (code "37") (name "Net-(R4-Pad1)") (class "Default")
      (node (ref "R4") (pin "1") (pinfunction "1_1") (pintype "passive"))
      (node (ref "R6") (pin "2") (pinfunction "2_2") (pintype "passive"))
    )
    (net (code "38") (name "Net-(R11-Pad2)") (class "Default")
      (node (ref "R11") (pin "2") (pinfunction "2_2") (pintype "passive"))
      (node (ref "R12") (pin "2") (pinfunction "2_2") (pintype "passive"))
    )
    (net (code "39") (name "Net-(R12-Pad1)") (class "Default")
      (node (ref "R12") (pin "1") (pinfunction "1_1") (pintype "passive"))
      (node (ref "R15") (pin "2") (pinfunction "2_2") (pintype "passive"))
    )
    (net (code "40") (name "Net-(U1-Out)") (class "Default")
      (node (ref "C17") (pin "2") (pinfunction "2_2") (pintype "passive"))
      (node (ref "C18") (pin "2") (pinfunction "2_2") (pintype "passive"))
      (node (ref "C7") (pin "2") (pinfunction "2_2") (pintype "passive"))
      (node (ref "C8") (pin "2") (pinfunction "2_2") (pintype "passive"))
      (node (ref "U1") (pin "2") (pinfunction "Out_2") (pintype "passive"))
      (node (ref "U2") (pin "13") (pinfunction "REFPQ_13") (pintype "passive"))
      (node (ref "U2") (pin "48") (pinfunction "REFPI_48") (pintype "passive"))
      (node (ref "VRef") (pin "1") (pinfunction "1_1") (pintype "passive"))
    )
    (net (code "41") (name "Net-(U2-INBI)") (class "Default")
      (node (ref "C22") (pin "1") (pinfunction "1_1") (pintype "passive"))
      (node (ref "L4") (pin "2") (pinfunction "2_2") (pintype "passive"))
      (node (ref "R5") (pin "2") (pinfunction "2_2") (pintype "passive"))
      (node (ref "U2") (pin "4") (pinfunction "INBI_4") (pintype "passive"))
    )
    (net (code "42") (name "Net-(U2-INBQ)") (class "Default")
      (node (ref "C28") (pin "1") (pinfunction "1_1") (pintype "passive"))
      (node (ref "L8") (pin "2") (pinfunction "2_2") (pintype "passive"))
      (node (ref "R13") (pin "2") (pinfunction "2_2") (pintype "passive"))
      (node (ref "U2") (pin "11") (pinfunction "INBQ_11") (pintype "passive"))
    )
    (net (code "43") (name "Net-(U2-INCMI)") (class "Default")
      (node (ref "C23") (pin "2") (pinfunction "2_2") (pintype "passive"))
      (node (ref "C24") (pin "2") (pinfunction "2_2") (pintype "passive"))
      (node (ref "U2") (pin "46") (pinfunction "INCMI_46") (pintype "passive"))
      (node (ref "U3") (pin "2") (pinfunction "VOCM_2") (pintype "passive"))
    )
    (net (code "44") (name "Net-(U2-INCMQ)") (class "Default")
      (node (ref "C29") (pin "2") (pinfunction "2_2") (pintype "passive"))
      (node (ref "C30") (pin "2") (pinfunction "2_2") (pintype "passive"))
      (node (ref "U2") (pin "15") (pinfunction "INCMQ_15") (pintype "passive"))
      (node (ref "U4") (pin "2") (pinfunction "VOCM_2") (pintype "passive"))
    )
    (net (code "45") (name "Net-(U2-INI)") (class "Default")
      (node (ref "C22") (pin "2") (pinfunction "2_2") (pintype "passive"))
      (node (ref "L2") (pin "2") (pinfunction "2_2") (pintype "passive"))
      (node (ref "R5") (pin "1") (pinfunction "1_1") (pintype "passive"))
      (node (ref "U2") (pin "2") (pinfunction "INI_2") (pintype "passive"))
    )
    (net (code "46") (name "Net-(U2-INQ)") (class "Default")
      (node (ref "C28") (pin "2") (pinfunction "2_2") (pintype "passive"))
      (node (ref "L6") (pin "2") (pinfunction "2_2") (pintype "passive"))
      (node (ref "R13") (pin "1") (pinfunction "1_1") (pintype "passive"))
      (node (ref "U2") (pin "9") (pinfunction "INQ_9") (pintype "passive"))
    )
    (net (code "47") (name "Net-(U2-IPOL)") (class "Default")
      (node (ref "R18") (pin "2") (pinfunction "2_2") (pintype "passive"))
      (node (ref "U2") (pin "6") (pinfunction "IPOL_6") (pintype "passive"))
    )
    (net (code "48") (name "Net-(U2-OEB)") (class "Default")
      (node (ref "R14") (pin "2") (pinfunction "2_2") (pintype "passive"))
      (node (ref "U2") (pin "43") (pinfunction "OEB_43") (pintype "passive"))
    )
    (net (code "49") (name "Net-(U2-SELECT)") (class "Default")
      (node (ref "R47") (pin "2") (pinfunction "2_2") (pintype "passive"))
      (node (ref "R48") (pin "1") (pinfunction "1_1") (pintype "passive"))
      (node (ref "U2") (pin "21") (pinfunction "SELECT_21") (pintype "passive"))
    )
    (net (code "50") (name "Net-(U3-IN+)") (class "Default")
      (node (ref "R6") (pin "1") (pinfunction "1_1") (pintype "passive"))
      (node (ref "R8") (pin "2") (pinfunction "2_2") (pintype "passive"))
      (node (ref "U3") (pin "8") (pinfunction "IN+_8") (pintype "passive"))
    )
    (net (code "51") (name "Net-(U3-IN-)") (class "Default")
      (node (ref "R1") (pin "2") (pinfunction "2_2") (pintype "passive"))
      (node (ref "R3") (pin "1") (pinfunction "1_1") (pintype "passive"))
      (node (ref "U3") (pin "1") (pinfunction "IN-_1") (pintype "passive"))
    )
    (net (code "52") (name "Net-(U3-OUT+)") (class "Default")
      (node (ref "R1") (pin "1") (pinfunction "1_1") (pintype "passive"))
      (node (ref "R2") (pin "2") (pinfunction "2_2") (pintype "passive"))
      (node (ref "U3") (pin "4") (pinfunction "OUT+_4") (pintype "passive"))
    )
    (net (code "53") (name "Net-(U3-OUT-)") (class "Default")
      (node (ref "R7") (pin "2") (pinfunction "2_2") (pintype "passive"))
      (node (ref "R8") (pin "1") (pinfunction "1_1") (pintype "passive"))
      (node (ref "U3") (pin "5") (pinfunction "OUT-_5") (pintype "passive"))
    )
    (net (code "54") (name "Net-(U4-IN+)") (class "Default")
      (node (ref "R15") (pin "1") (pinfunction "1_1") (pintype "passive"))
      (node (ref "R17") (pin "2") (pinfunction "2_2") (pintype "passive"))
      (node (ref "U4") (pin "8") (pinfunction "IN+_8") (pintype "passive"))
    )
    (net (code "55") (name "Net-(U4-IN-)") (class "Default")
      (node (ref "R11") (pin "1") (pinfunction "1_1") (pintype "passive"))
      (node (ref "R9") (pin "2") (pinfunction "2_2") (pintype "passive"))
      (node (ref "U4") (pin "1") (pinfunction "IN-_1") (pintype "passive"))
    )
    (net (code "56") (name "Net-(U4-OUT+)") (class "Default")
      (node (ref "R10") (pin "2") (pinfunction "2_2") (pintype "passive"))
      (node (ref "R9") (pin "1") (pinfunction "1_1") (pintype "passive"))
      (node (ref "U4") (pin "4") (pinfunction "OUT+_4") (pintype "passive"))
    )
    (net (code "57") (name "Net-(U4-OUT-)") (class "Default")
      (node (ref "R16") (pin "2") (pinfunction "2_2") (pintype "passive"))
      (node (ref "R17") (pin "1") (pinfunction "1_1") (pintype "passive"))
      (node (ref "U4") (pin "5") (pinfunction "OUT-_5") (pintype "passive"))
    )
    (net (code "58") (name "unconnected-(U3-NC-Pad7)") (class "Default")
      (node (ref "U3") (pin "7") (pinfunction "NC_7") (pintype "passive"))
    )
    (net (code "59") (name "unconnected-(U4-NC-Pad7)") (class "Default")
      (node (ref "U4") (pin "7") (pinfunction "NC_7") (pintype "passive"))
    )
  )
)
